# MCU2.net
KiCad netlist of a schematic drawn in Altium Designer
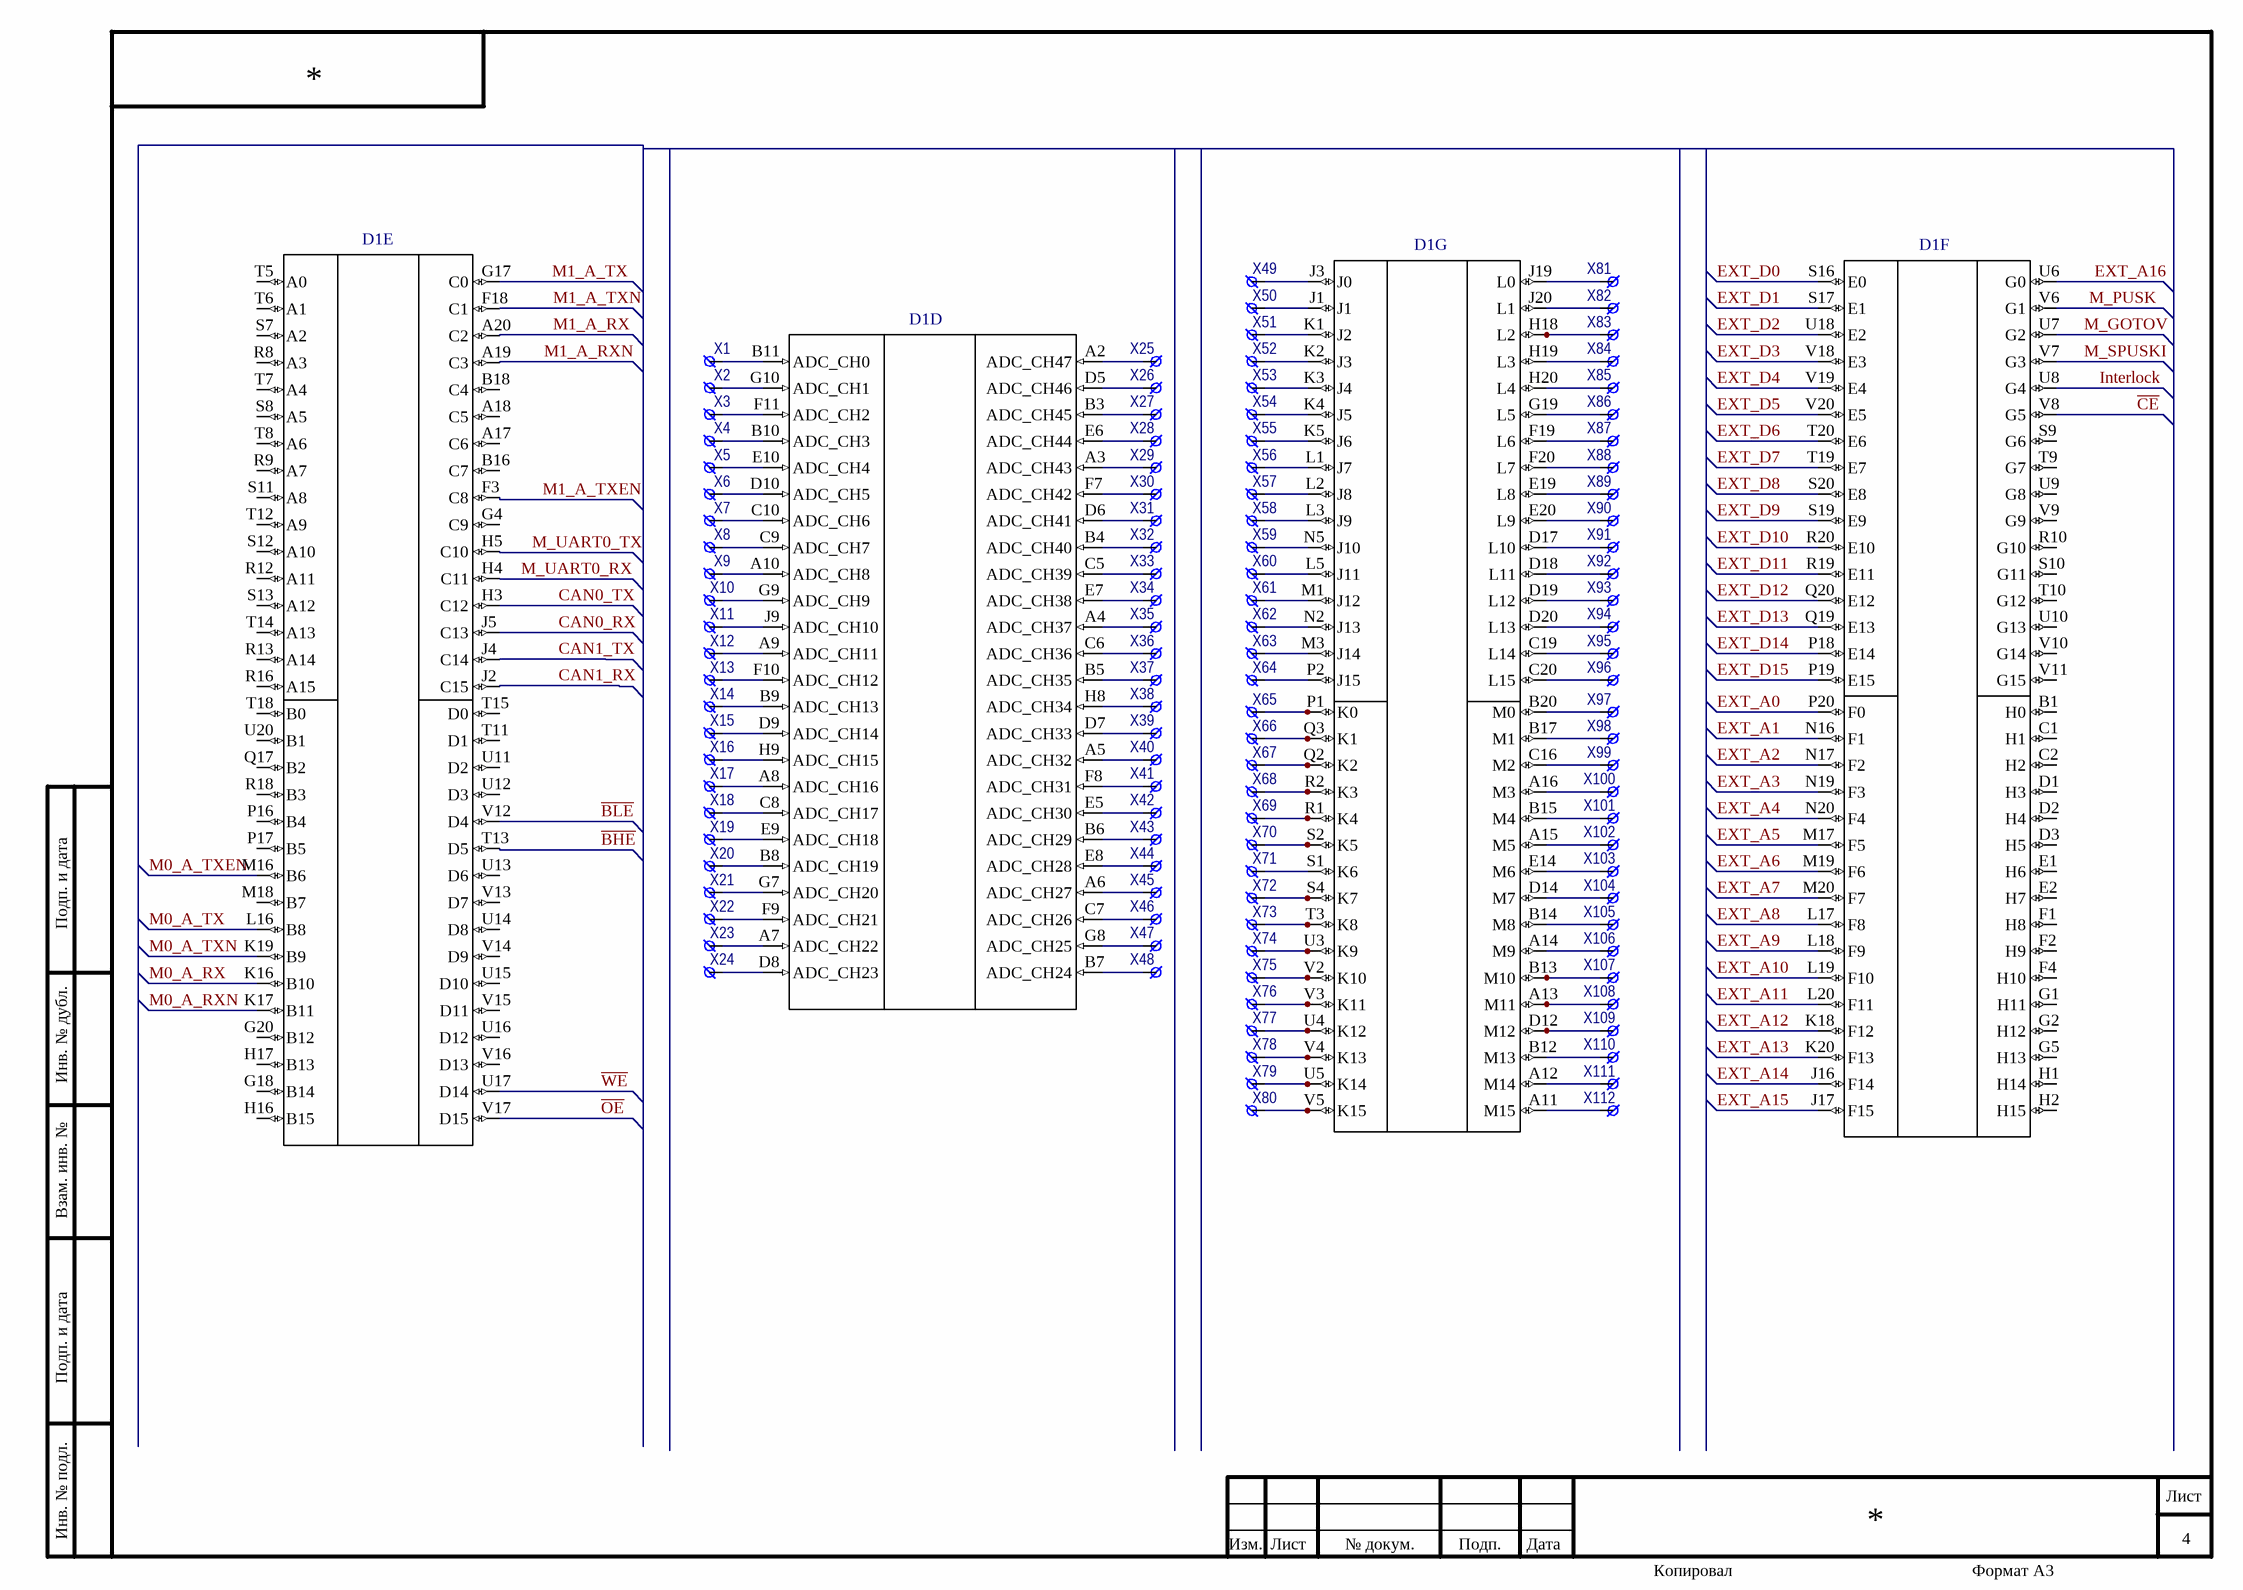
[diagram p0: MCU2.SchDoc]

(export (version "E")
  (design (tool "Eeschema 10.0.6"))
  (components
    (comp (ref "D1")
      (value "1921ВК028")
      (footprint "BGA-400_21.0X21.0MM_LAYOUT20X20_P1.0MM")
      (description "МК 1921ВК028")
      (libsource (lib "Блок вычислительный") (part "1921ВК028"))
    )
    (comp (ref "X1")
      (value "CONT")
      (footprint "ПЛАН_ПЛОЩ")
      (description "CONT1_SMD")
      (fields (field (name "PARTNUMBER") "контактное поле"))
      (libsource (lib "Блок вычислительный") (part "CONT"))
    )
    (comp (ref "X2")
      (value "CONT")
      (footprint "ПЛАН_ПЛОЩ")
      (description "CONT1_SMD")
      (fields (field (name "PARTNUMBER") "контактное поле"))
      (libsource (lib "Блок вычислительный") (part "CONT"))
    )
    (comp (ref "X3")
      (value "CONT")
      (footprint "ПЛАН_ПЛОЩ")
      (description "CONT1_SMD")
      (fields (field (name "PARTNUMBER") "контактное поле"))
      (libsource (lib "Блок вычислительный") (part "CONT"))
    )
    (comp (ref "X4")
      (value "CONT")
      (footprint "ПЛАН_ПЛОЩ")
      (description "CONT1_SMD")
      (fields (field (name "PARTNUMBER") "контактное поле"))
      (libsource (lib "Блок вычислительный") (part "CONT"))
    )
    (comp (ref "X5")
      (value "CONT")
      (footprint "ПЛАН_ПЛОЩ")
      (description "CONT1_SMD")
      (fields (field (name "PARTNUMBER") "контактное поле"))
      (libsource (lib "Блок вычислительный") (part "CONT"))
    )
    (comp (ref "X6")
      (value "CONT")
      (footprint "ПЛАН_ПЛОЩ")
      (description "CONT1_SMD")
      (fields (field (name "PARTNUMBER") "контактное поле"))
      (libsource (lib "Блок вычислительный") (part "CONT"))
    )
    (comp (ref "X7")
      (value "CONT")
      (footprint "ПЛАН_ПЛОЩ")
      (description "CONT1_SMD")
      (fields (field (name "PARTNUMBER") "контактное поле"))
      (libsource (lib "Блок вычислительный") (part "CONT"))
    )
    (comp (ref "X8")
      (value "CONT")
      (footprint "ПЛАН_ПЛОЩ")
      (description "CONT1_SMD")
      (fields (field (name "PARTNUMBER") "контактное поле"))
      (libsource (lib "Блок вычислительный") (part "CONT"))
    )
    (comp (ref "X9")
      (value "CONT")
      (footprint "ПЛАН_ПЛОЩ")
      (description "CONT1_SMD")
      (fields (field (name "PARTNUMBER") "контактное поле"))
      (libsource (lib "Блок вычислительный") (part "CONT"))
    )
    (comp (ref "X10")
      (value "CONT")
      (footprint "ПЛАН_ПЛОЩ")
      (description "CONT1_SMD")
      (fields (field (name "PARTNUMBER") "контактное поле"))
      (libsource (lib "Блок вычислительный") (part "CONT"))
    )
    (comp (ref "X11")
      (value "CONT")
      (footprint "ПЛАН_ПЛОЩ")
      (description "CONT1_SMD")
      (fields (field (name "PARTNUMBER") "контактное поле"))
      (libsource (lib "Блок вычислительный") (part "CONT"))
    )
    (comp (ref "X12")
      (value "CONT")
      (footprint "ПЛАН_ПЛОЩ")
      (description "CONT1_SMD")
      (fields (field (name "PARTNUMBER") "контактное поле"))
      (libsource (lib "Блок вычислительный") (part "CONT"))
    )
    (comp (ref "X13")
      (value "CONT")
      (footprint "ПЛАН_ПЛОЩ")
      (description "CONT1_SMD")
      (fields (field (name "PARTNUMBER") "контактное поле"))
      (libsource (lib "Блок вычислительный") (part "CONT"))
    )
    (comp (ref "X14")
      (value "CONT")
      (footprint "ПЛАН_ПЛОЩ")
      (description "CONT1_SMD")
      (fields (field (name "PARTNUMBER") "контактное поле"))
      (libsource (lib "Блок вычислительный") (part "CONT"))
    )
    (comp (ref "X15")
      (value "CONT")
      (footprint "ПЛАН_ПЛОЩ")
      (description "CONT1_SMD")
      (fields (field (name "PARTNUMBER") "контактное поле"))
      (libsource (lib "Блок вычислительный") (part "CONT"))
    )
    (comp (ref "X16")
      (value "CONT")
      (footprint "ПЛАН_ПЛОЩ")
      (description "CONT1_SMD")
      (fields (field (name "PARTNUMBER") "контактное поле"))
      (libsource (lib "Блок вычислительный") (part "CONT"))
    )
    (comp (ref "X17")
      (value "CONT")
      (footprint "ПЛАН_ПЛОЩ")
      (description "CONT1_SMD")
      (fields (field (name "PARTNUMBER") "контактное поле"))
      (libsource (lib "Блок вычислительный") (part "CONT"))
    )
    (comp (ref "X18")
      (value "CONT")
      (footprint "ПЛАН_ПЛОЩ")
      (description "CONT1_SMD")
      (fields (field (name "PARTNUMBER") "контактное поле"))
      (libsource (lib "Блок вычислительный") (part "CONT"))
    )
    (comp (ref "X19")
      (value "CONT")
      (footprint "ПЛАН_ПЛОЩ")
      (description "CONT1_SMD")
      (fields (field (name "PARTNUMBER") "контактное поле"))
      (libsource (lib "Блок вычислительный") (part "CONT"))
    )
    (comp (ref "X20")
      (value "CONT")
      (footprint "ПЛАН_ПЛОЩ")
      (description "CONT1_SMD")
      (fields (field (name "PARTNUMBER") "контактное поле"))
      (libsource (lib "Блок вычислительный") (part "CONT"))
    )
    (comp (ref "X21")
      (value "CONT")
      (footprint "ПЛАН_ПЛОЩ")
      (description "CONT1_SMD")
      (fields (field (name "PARTNUMBER") "контактное поле"))
      (libsource (lib "Блок вычислительный") (part "CONT"))
    )
    (comp (ref "X22")
      (value "CONT")
      (footprint "ПЛАН_ПЛОЩ")
      (description "CONT1_SMD")
      (fields (field (name "PARTNUMBER") "контактное поле"))
      (libsource (lib "Блок вычислительный") (part "CONT"))
    )
    (comp (ref "X23")
      (value "CONT")
      (footprint "ПЛАН_ПЛОЩ")
      (description "CONT1_SMD")
      (fields (field (name "PARTNUMBER") "контактное поле"))
      (libsource (lib "Блок вычислительный") (part "CONT"))
    )
    (comp (ref "X24")
      (value "CONT")
      (footprint "ПЛАН_ПЛОЩ")
      (description "CONT1_SMD")
      (fields (field (name "PARTNUMBER") "контактное поле"))
      (libsource (lib "Блок вычислительный") (part "CONT"))
    )
    (comp (ref "X25")
      (value "CONT")
      (footprint "ПЛАН_ПЛОЩ")
      (description "CONT1_SMD")
      (fields (field (name "PARTNUMBER") "контактное поле"))
      (libsource (lib "Блок вычислительный") (part "CONT"))
    )
    (comp (ref "X26")
      (value "CONT")
      (footprint "ПЛАН_ПЛОЩ")
      (description "CONT1_SMD")
      (fields (field (name "PARTNUMBER") "контактное поле"))
      (libsource (lib "Блок вычислительный") (part "CONT"))
    )
    (comp (ref "X27")
      (value "CONT")
      (footprint "ПЛАН_ПЛОЩ")
      (description "CONT1_SMD")
      (fields (field (name "PARTNUMBER") "контактное поле"))
      (libsource (lib "Блок вычислительный") (part "CONT"))
    )
    (comp (ref "X28")
      (value "CONT")
      (footprint "ПЛАН_ПЛОЩ")
      (description "CONT1_SMD")
      (fields (field (name "PARTNUMBER") "контактное поле"))
      (libsource (lib "Блок вычислительный") (part "CONT"))
    )
    (comp (ref "X29")
      (value "CONT")
      (footprint "ПЛАН_ПЛОЩ")
      (description "CONT1_SMD")
      (fields (field (name "PARTNUMBER") "контактное поле"))
      (libsource (lib "Блок вычислительный") (part "CONT"))
    )
    (comp (ref "X30")
      (value "CONT")
      (footprint "ПЛАН_ПЛОЩ")
      (description "CONT1_SMD")
      (fields (field (name "PARTNUMBER") "контактное поле"))
      (libsource (lib "Блок вычислительный") (part "CONT"))
    )
    (comp (ref "X31")
      (value "CONT")
      (footprint "ПЛАН_ПЛОЩ")
      (description "CONT1_SMD")
      (fields (field (name "PARTNUMBER") "контактное поле"))
      (libsource (lib "Блок вычислительный") (part "CONT"))
    )
    (comp (ref "X32")
      (value "CONT")
      (footprint "ПЛАН_ПЛОЩ")
      (description "CONT1_SMD")
      (fields (field (name "PARTNUMBER") "контактное поле"))
      (libsource (lib "Блок вычислительный") (part "CONT"))
    )
    (comp (ref "X33")
      (value "CONT")
      (footprint "ПЛАН_ПЛОЩ")
      (description "CONT1_SMD")
      (fields (field (name "PARTNUMBER") "контактное поле"))
      (libsource (lib "Блок вычислительный") (part "CONT"))
    )
    (comp (ref "X34")
      (value "CONT")
      (footprint "ПЛАН_ПЛОЩ")
      (description "CONT1_SMD")
      (fields (field (name "PARTNUMBER") "контактное поле"))
      (libsource (lib "Блок вычислительный") (part "CONT"))
    )
    (comp (ref "X35")
      (value "CONT")
      (footprint "ПЛАН_ПЛОЩ")
      (description "CONT1_SMD")
      (fields (field (name "PARTNUMBER") "контактное поле"))
      (libsource (lib "Блок вычислительный") (part "CONT"))
    )
    (comp (ref "X36")
      (value "CONT")
      (footprint "ПЛАН_ПЛОЩ")
      (description "CONT1_SMD")
      (fields (field (name "PARTNUMBER") "контактное поле"))
      (libsource (lib "Блок вычислительный") (part "CONT"))
    )
    (comp (ref "X37")
      (value "CONT")
      (footprint "ПЛАН_ПЛОЩ")
      (description "CONT1_SMD")
      (fields (field (name "PARTNUMBER") "контактное поле"))
      (libsource (lib "Блок вычислительный") (part "CONT"))
    )
    (comp (ref "X38")
      (value "CONT")
      (footprint "ПЛАН_ПЛОЩ")
      (description "CONT1_SMD")
      (fields (field (name "PARTNUMBER") "контактное поле"))
      (libsource (lib "Блок вычислительный") (part "CONT"))
    )
    (comp (ref "X39")
      (value "CONT")
      (footprint "ПЛАН_ПЛОЩ")
      (description "CONT1_SMD")
      (fields (field (name "PARTNUMBER") "контактное поле"))
      (libsource (lib "Блок вычислительный") (part "CONT"))
    )
    (comp (ref "X40")
      (value "CONT")
      (footprint "ПЛАН_ПЛОЩ")
      (description "CONT1_SMD")
      (fields (field (name "PARTNUMBER") "контактное поле"))
      (libsource (lib "Блок вычислительный") (part "CONT"))
    )
    (comp (ref "X41")
      (value "CONT")
      (footprint "ПЛАН_ПЛОЩ")
      (description "CONT1_SMD")
      (fields (field (name "PARTNUMBER") "контактное поле"))
      (libsource (lib "Блок вычислительный") (part "CONT"))
    )
    (comp (ref "X42")
      (value "CONT")
      (footprint "ПЛАН_ПЛОЩ")
      (description "CONT1_SMD")
      (fields (field (name "PARTNUMBER") "контактное поле"))
      (libsource (lib "Блок вычислительный") (part "CONT"))
    )
    (comp (ref "X43")
      (value "CONT")
      (footprint "ПЛАН_ПЛОЩ")
      (description "CONT1_SMD")
      (fields (field (name "PARTNUMBER") "контактное поле"))
      (libsource (lib "Блок вычислительный") (part "CONT"))
    )
    (comp (ref "X44")
      (value "CONT")
      (footprint "ПЛАН_ПЛОЩ")
      (description "CONT1_SMD")
      (fields (field (name "PARTNUMBER") "контактное поле"))
      (libsource (lib "Блок вычислительный") (part "CONT"))
    )
    (comp (ref "X45")
      (value "CONT")
      (footprint "ПЛАН_ПЛОЩ")
      (description "CONT1_SMD")
      (fields (field (name "PARTNUMBER") "контактное поле"))
      (libsource (lib "Блок вычислительный") (part "CONT"))
    )
    (comp (ref "X46")
      (value "CONT")
      (footprint "ПЛАН_ПЛОЩ")
      (description "CONT1_SMD")
      (fields (field (name "PARTNUMBER") "контактное поле"))
      (libsource (lib "Блок вычислительный") (part "CONT"))
    )
    (comp (ref "X47")
      (value "CONT")
      (footprint "ПЛАН_ПЛОЩ")
      (description "CONT1_SMD")
      (fields (field (name "PARTNUMBER") "контактное поле"))
      (libsource (lib "Блок вычислительный") (part "CONT"))
    )
    (comp (ref "X48")
      (value "CONT")
      (footprint "ПЛАН_ПЛОЩ")
      (description "CONT1_SMD")
      (fields (field (name "PARTNUMBER") "контактное поле"))
      (libsource (lib "Блок вычислительный") (part "CONT"))
    )
    (comp (ref "X49")
      (value "CONT")
      (footprint "ПЛАН_ПЛОЩ")
      (description "CONT1_SMD")
      (fields (field (name "PARTNUMBER") "контактное поле"))
      (libsource (lib "Блок вычислительный") (part "CONT"))
    )
    (comp (ref "X50")
      (value "CONT")
      (footprint "ПЛАН_ПЛОЩ")
      (description "CONT1_SMD")
      (fields (field (name "PARTNUMBER") "контактное поле"))
      (libsource (lib "Блок вычислительный") (part "CONT"))
    )
    (comp (ref "X51")
      (value "CONT")
      (footprint "ПЛАН_ПЛОЩ")
      (description "CONT1_SMD")
      (fields (field (name "PARTNUMBER") "контактное поле"))
      (libsource (lib "Блок вычислительный") (part "CONT"))
    )
    (comp (ref "X52")
      (value "CONT")
      (footprint "ПЛАН_ПЛОЩ")
      (description "CONT1_SMD")
      (fields (field (name "PARTNUMBER") "контактное поле"))
      (libsource (lib "Блок вычислительный") (part "CONT"))
    )
    (comp (ref "X53")
      (value "CONT")
      (footprint "ПЛАН_ПЛОЩ")
      (description "CONT1_SMD")
      (fields (field (name "PARTNUMBER") "контактное поле"))
      (libsource (lib "Блок вычислительный") (part "CONT"))
    )
    (comp (ref "X54")
      (value "CONT")
      (footprint "ПЛАН_ПЛОЩ")
      (description "CONT1_SMD")
      (fields (field (name "PARTNUMBER") "контактное поле"))
      (libsource (lib "Блок вычислительный") (part "CONT"))
    )
    (comp (ref "X55")
      (value "CONT")
      (footprint "ПЛАН_ПЛОЩ")
      (description "CONT1_SMD")
      (fields (field (name "PARTNUMBER") "контактное поле"))
      (libsource (lib "Блок вычислительный") (part "CONT"))
    )
    (comp (ref "X56")
      (value "CONT")
      (footprint "ПЛАН_ПЛОЩ")
      (description "CONT1_SMD")
      (fields (field (name "PARTNUMBER") "контактное поле"))
      (libsource (lib "Блок вычислительный") (part "CONT"))
    )
    (comp (ref "X57")
      (value "CONT")
      (footprint "ПЛАН_ПЛОЩ")
      (description "CONT1_SMD")
      (fields (field (name "PARTNUMBER") "контактное поле"))
      (libsource (lib "Блок вычислительный") (part "CONT"))
    )
    (comp (ref "X58")
      (value "CONT")
      (footprint "ПЛАН_ПЛОЩ")
      (description "CONT1_SMD")
      (fields (field (name "PARTNUMBER") "контактное поле"))
      (libsource (lib "Блок вычислительный") (part "CONT"))
    )
    (comp (ref "X59")
      (value "CONT")
      (footprint "ПЛАН_ПЛОЩ")
      (description "CONT1_SMD")
      (fields (field (name "PARTNUMBER") "контактное поле"))
      (libsource (lib "Блок вычислительный") (part "CONT"))
    )
    (comp (ref "X60")
      (value "CONT")
      (footprint "ПЛАН_ПЛОЩ")
      (description "CONT1_SMD")
      (fields (field (name "PARTNUMBER") "контактное поле"))
      (libsource (lib "Блок вычислительный") (part "CONT"))
    )
    (comp (ref "X61")
      (value "CONT")
      (footprint "ПЛАН_ПЛОЩ")
      (description "CONT1_SMD")
      (fields (field (name "PARTNUMBER") "контактное поле"))
      (libsource (lib "Блок вычислительный") (part "CONT"))
    )
    (comp (ref "X62")
      (value "CONT")
      (footprint "ПЛАН_ПЛОЩ")
      (description "CONT1_SMD")
      (fields (field (name "PARTNUMBER") "контактное поле"))
      (libsource (lib "Блок вычислительный") (part "CONT"))
    )
    (comp (ref "X63")
      (value "CONT")
      (footprint "ПЛАН_ПЛОЩ")
      (description "CONT1_SMD")
      (fields (field (name "PARTNUMBER") "контактное поле"))
      (libsource (lib "Блок вычислительный") (part "CONT"))
    )
    (comp (ref "X64")
      (value "CONT")
      (footprint "ПЛАН_ПЛОЩ")
      (description "CONT1_SMD")
      (fields (field (name "PARTNUMBER") "контактное поле"))
      (libsource (lib "Блок вычислительный") (part "CONT"))
    )
    (comp (ref "X65")
      (value "CONT")
      (footprint "ПЛАН_ПЛОЩ")
      (description "CONT1_SMD")
      (fields (field (name "PARTNUMBER") "контактное поле"))
      (libsource (lib "Блок вычислительный") (part "CONT"))
    )
    (comp (ref "X66")
      (value "CONT")
      (footprint "ПЛАН_ПЛОЩ")
      (description "CONT1_SMD")
      (fields (field (name "PARTNUMBER") "контактное поле"))
      (libsource (lib "Блок вычислительный") (part "CONT"))
    )
    (comp (ref "X67")
      (value "CONT")
      (footprint "ПЛАН_ПЛОЩ")
      (description "CONT1_SMD")
      (fields (field (name "PARTNUMBER") "контактное поле"))
      (libsource (lib "Блок вычислительный") (part "CONT"))
    )
    (comp (ref "X68")
      (value "CONT")
      (footprint "ПЛАН_ПЛОЩ")
      (description "CONT1_SMD")
      (fields (field (name "PARTNUMBER") "контактное поле"))
      (libsource (lib "Блок вычислительный") (part "CONT"))
    )
    (comp (ref "X69")
      (value "CONT")
      (footprint "ПЛАН_ПЛОЩ")
      (description "CONT1_SMD")
      (fields (field (name "PARTNUMBER") "контактное поле"))
      (libsource (lib "Блок вычислительный") (part "CONT"))
    )
    (comp (ref "X70")
      (value "CONT")
      (footprint "ПЛАН_ПЛОЩ")
      (description "CONT1_SMD")
      (fields (field (name "PARTNUMBER") "контактное поле"))
      (libsource (lib "Блок вычислительный") (part "CONT"))
    )
    (comp (ref "X71")
      (value "CONT")
      (footprint "ПЛАН_ПЛОЩ")
      (description "CONT1_SMD")
      (fields (field (name "PARTNUMBER") "контактное поле"))
      (libsource (lib "Блок вычислительный") (part "CONT"))
    )
    (comp (ref "X72")
      (value "CONT")
      (footprint "ПЛАН_ПЛОЩ")
      (description "CONT1_SMD")
      (fields (field (name "PARTNUMBER") "контактное поле"))
      (libsource (lib "Блок вычислительный") (part "CONT"))
    )
    (comp (ref "X73")
      (value "CONT")
      (footprint "ПЛАН_ПЛОЩ")
      (description "CONT1_SMD")
      (fields (field (name "PARTNUMBER") "контактное поле"))
      (libsource (lib "Блок вычислительный") (part "CONT"))
    )
    (comp (ref "X74")
      (value "CONT")
      (footprint "ПЛАН_ПЛОЩ")
      (description "CONT1_SMD")
      (fields (field (name "PARTNUMBER") "контактное поле"))
      (libsource (lib "Блок вычислительный") (part "CONT"))
    )
    (comp (ref "X75")
      (value "CONT")
      (footprint "ПЛАН_ПЛОЩ")
      (description "CONT1_SMD")
      (fields (field (name "PARTNUMBER") "контактное поле"))
      (libsource (lib "Блок вычислительный") (part "CONT"))
    )
    (comp (ref "X76")
      (value "CONT")
      (footprint "ПЛАН_ПЛОЩ")
      (description "CONT1_SMD")
      (fields (field (name "PARTNUMBER") "контактное поле"))
      (libsource (lib "Блок вычислительный") (part "CONT"))
    )
    (comp (ref "X77")
      (value "CONT")
      (footprint "ПЛАН_ПЛОЩ")
      (description "CONT1_SMD")
      (fields (field (name "PARTNUMBER") "контактное поле"))
      (libsource (lib "Блок вычислительный") (part "CONT"))
    )
    (comp (ref "X78")
      (value "CONT")
      (footprint "ПЛАН_ПЛОЩ")
      (description "CONT1_SMD")
      (fields (field (name "PARTNUMBER") "контактное поле"))
      (libsource (lib "Блок вычислительный") (part "CONT"))
    )
    (comp (ref "X79")
      (value "CONT")
      (footprint "ПЛАН_ПЛОЩ")
      (description "CONT1_SMD")
      (fields (field (name "PARTNUMBER") "контактное поле"))
      (libsource (lib "Блок вычислительный") (part "CONT"))
    )
    (comp (ref "X80")
      (value "CONT")
      (footprint "ПЛАН_ПЛОЩ")
      (description "CONT1_SMD")
      (fields (field (name "PARTNUMBER") "контактное поле"))
      (libsource (lib "Блок вычислительный") (part "CONT"))
    )
    (comp (ref "X81")
      (value "CONT")
      (footprint "ПЛАН_ПЛОЩ")
      (description "CONT1_SMD")
      (fields (field (name "PARTNUMBER") "контактное поле"))
      (libsource (lib "Блок вычислительный") (part "CONT"))
    )
    (comp (ref "X82")
      (value "CONT")
      (footprint "ПЛАН_ПЛОЩ")
      (description "CONT1_SMD")
      (fields (field (name "PARTNUMBER") "контактное поле"))
      (libsource (lib "Блок вычислительный") (part "CONT"))
    )
    (comp (ref "X83")
      (value "CONT")
      (footprint "ПЛАН_ПЛОЩ")
      (description "CONT1_SMD")
      (fields (field (name "PARTNUMBER") "контактное поле"))
      (libsource (lib "Блок вычислительный") (part "CONT"))
    )
    (comp (ref "X84")
      (value "CONT")
      (footprint "ПЛАН_ПЛОЩ")
      (description "CONT1_SMD")
      (fields (field (name "PARTNUMBER") "контактное поле"))
      (libsource (lib "Блок вычислительный") (part "CONT"))
    )
    (comp (ref "X85")
      (value "CONT")
      (footprint "ПЛАН_ПЛОЩ")
      (description "CONT1_SMD")
      (fields (field (name "PARTNUMBER") "контактное поле"))
      (libsource (lib "Блок вычислительный") (part "CONT"))
    )
    (comp (ref "X86")
      (value "CONT")
      (footprint "ПЛАН_ПЛОЩ")
      (description "CONT1_SMD")
      (fields (field (name "PARTNUMBER") "контактное поле"))
      (libsource (lib "Блок вычислительный") (part "CONT"))
    )
    (comp (ref "X87")
      (value "CONT")
      (footprint "ПЛАН_ПЛОЩ")
      (description "CONT1_SMD")
      (fields (field (name "PARTNUMBER") "контактное поле"))
      (libsource (lib "Блок вычислительный") (part "CONT"))
    )
    (comp (ref "X88")
      (value "CONT")
      (footprint "ПЛАН_ПЛОЩ")
      (description "CONT1_SMD")
      (fields (field (name "PARTNUMBER") "контактное поле"))
      (libsource (lib "Блок вычислительный") (part "CONT"))
    )
    (comp (ref "X89")
      (value "CONT")
      (footprint "ПЛАН_ПЛОЩ")
      (description "CONT1_SMD")
      (fields (field (name "PARTNUMBER") "контактное поле"))
      (libsource (lib "Блок вычислительный") (part "CONT"))
    )
    (comp (ref "X90")
      (value "CONT")
      (footprint "ПЛАН_ПЛОЩ")
      (description "CONT1_SMD")
      (fields (field (name "PARTNUMBER") "контактное поле"))
      (libsource (lib "Блок вычислительный") (part "CONT"))
    )
    (comp (ref "X91")
      (value "CONT")
      (footprint "ПЛАН_ПЛОЩ")
      (description "CONT1_SMD")
      (fields (field (name "PARTNUMBER") "контактное поле"))
      (libsource (lib "Блок вычислительный") (part "CONT"))
    )
    (comp (ref "X92")
      (value "CONT")
      (footprint "ПЛАН_ПЛОЩ")
      (description "CONT1_SMD")
      (fields (field (name "PARTNUMBER") "контактное поле"))
      (libsource (lib "Блок вычислительный") (part "CONT"))
    )
    (comp (ref "X93")
      (value "CONT")
      (footprint "ПЛАН_ПЛОЩ")
      (description "CONT1_SMD")
      (fields (field (name "PARTNUMBER") "контактное поле"))
      (libsource (lib "Блок вычислительный") (part "CONT"))
    )
    (comp (ref "X94")
      (value "CONT")
      (footprint "ПЛАН_ПЛОЩ")
      (description "CONT1_SMD")
      (fields (field (name "PARTNUMBER") "контактное поле"))
      (libsource (lib "Блок вычислительный") (part "CONT"))
    )
    (comp (ref "X95")
      (value "CONT")
      (footprint "ПЛАН_ПЛОЩ")
      (description "CONT1_SMD")
      (fields (field (name "PARTNUMBER") "контактное поле"))
      (libsource (lib "Блок вычислительный") (part "CONT"))
    )
    (comp (ref "X96")
      (value "CONT")
      (footprint "ПЛАН_ПЛОЩ")
      (description "CONT1_SMD")
      (fields (field (name "PARTNUMBER") "контактное поле"))
      (libsource (lib "Блок вычислительный") (part "CONT"))
    )
    (comp (ref "X97")
      (value "CONT")
      (footprint "ПЛАН_ПЛОЩ")
      (description "CONT1_SMD")
      (fields (field (name "PARTNUMBER") "контактное поле"))
      (libsource (lib "Блок вычислительный") (part "CONT"))
    )
    (comp (ref "X98")
      (value "CONT")
      (footprint "ПЛАН_ПЛОЩ")
      (description "CONT1_SMD")
      (fields (field (name "PARTNUMBER") "контактное поле"))
      (libsource (lib "Блок вычислительный") (part "CONT"))
    )
    (comp (ref "X99")
      (value "CONT")
      (footprint "ПЛАН_ПЛОЩ")
      (description "CONT1_SMD")
      (fields (field (name "PARTNUMBER") "контактное поле"))
      (libsource (lib "Блок вычислительный") (part "CONT"))
    )
    (comp (ref "X100")
      (value "CONT")
      (footprint "ПЛАН_ПЛОЩ")
      (description "CONT1_SMD")
      (fields (field (name "PARTNUMBER") "контактное поле"))
      (libsource (lib "Блок вычислительный") (part "CONT"))
    )
    (comp (ref "X101")
      (value "CONT")
      (footprint "ПЛАН_ПЛОЩ")
      (description "CONT1_SMD")
      (fields (field (name "PARTNUMBER") "контактное поле"))
      (libsource (lib "Блок вычислительный") (part "CONT"))
    )
    (comp (ref "X102")
      (value "CONT")
      (footprint "ПЛАН_ПЛОЩ")
      (description "CONT1_SMD")
      (fields (field (name "PARTNUMBER") "контактное поле"))
      (libsource (lib "Блок вычислительный") (part "CONT"))
    )
    (comp (ref "X103")
      (value "CONT")
      (footprint "ПЛАН_ПЛОЩ")
      (description "CONT1_SMD")
      (fields (field (name "PARTNUMBER") "контактное поле"))
      (libsource (lib "Блок вычислительный") (part "CONT"))
    )
    (comp (ref "X104")
      (value "CONT")
      (footprint "ПЛАН_ПЛОЩ")
      (description "CONT1_SMD")
      (fields (field (name "PARTNUMBER") "контактное поле"))
      (libsource (lib "Блок вычислительный") (part "CONT"))
    )
    (comp (ref "X105")
      (value "CONT")
      (footprint "ПЛАН_ПЛОЩ")
      (description "CONT1_SMD")
      (fields (field (name "PARTNUMBER") "контактное поле"))
      (libsource (lib "Блок вычислительный") (part "CONT"))
    )
    (comp (ref "X106")
      (value "CONT")
      (footprint "ПЛАН_ПЛОЩ")
      (description "CONT1_SMD")
      (fields (field (name "PARTNUMBER") "контактное поле"))
      (libsource (lib "Блок вычислительный") (part "CONT"))
    )
    (comp (ref "X107")
      (value "CONT")
      (footprint "ПЛАН_ПЛОЩ")
      (description "CONT1_SMD")
      (fields (field (name "PARTNUMBER") "контактное поле"))
      (libsource (lib "Блок вычислительный") (part "CONT"))
    )
    (comp (ref "X108")
      (value "CONT")
      (footprint "ПЛАН_ПЛОЩ")
      (description "CONT1_SMD")
      (fields (field (name "PARTNUMBER") "контактное поле"))
      (libsource (lib "Блок вычислительный") (part "CONT"))
    )
    (comp (ref "X109")
      (value "CONT")
      (footprint "ПЛАН_ПЛОЩ")
      (description "CONT1_SMD")
      (fields (field (name "PARTNUMBER") "контактное поле"))
      (libsource (lib "Блок вычислительный") (part "CONT"))
    )
    (comp (ref "X110")
      (value "CONT")
      (footprint "ПЛАН_ПЛОЩ")
      (description "CONT1_SMD")
      (fields (field (name "PARTNUMBER") "контактное поле"))
      (libsource (lib "Блок вычислительный") (part "CONT"))
    )
    (comp (ref "X111")
      (value "CONT")
      (footprint "ПЛАН_ПЛОЩ")
      (description "CONT1_SMD")
      (fields (field (name "PARTNUMBER") "контактное поле"))
      (libsource (lib "Блок вычислительный") (part "CONT"))
    )
    (comp (ref "X112")
      (value "CONT")
      (footprint "ПЛАН_ПЛОЩ")
      (description "CONT1_SMD")
      (fields (field (name "PARTNUMBER") "контактное поле"))
      (libsource (lib "Блок вычислительный") (part "CONT"))
    )
  )
  (nets
    (net (code "1") (name "/BHE") (class "Default")
      (node (ref "D1") (pin "T13") (pinfunction "D5_T13") (pintype "bidirectional"))
    )
    (net (code "2") (name "/BLE") (class "Default")
      (node (ref "D1") (pin "V12") (pinfunction "D4_V12") (pintype "bidirectional"))
    )
    (net (code "3") (name "/CAN0_RX") (class "Default")
      (node (ref "D1") (pin "J5") (pinfunction "C13_J5") (pintype "bidirectional"))
    )
    (net (code "4") (name "/CAN0_TX") (class "Default")
      (node (ref "D1") (pin "H3") (pinfunction "C12_H3") (pintype "bidirectional"))
    )
    (net (code "5") (name "/CAN1_RX") (class "Default")
      (node (ref "D1") (pin "J2") (pinfunction "C15_J2") (pintype "bidirectional"))
    )
    (net (code "6") (name "/CAN1_TX") (class "Default")
      (node (ref "D1") (pin "J4") (pinfunction "C14_J4") (pintype "bidirectional"))
    )
    (net (code "7") (name "/CE") (class "Default")
      (node (ref "D1") (pin "V8") (pinfunction "G5_V8") (pintype "bidirectional"))
    )
    (net (code "8") (name "/EXT_A0") (class "Default")
      (node (ref "D1") (pin "P20") (pinfunction "F0_P20") (pintype "bidirectional"))
    )
    (net (code "9") (name "/EXT_A1") (class "Default")
      (node (ref "D1") (pin "N16") (pinfunction "F1_N16") (pintype "bidirectional"))
    )
    (net (code "10") (name "/EXT_A2") (class "Default")
      (node (ref "D1") (pin "N17") (pinfunction "F2_N17") (pintype "bidirectional"))
    )
    (net (code "11") (name "/EXT_A3") (class "Default")
      (node (ref "D1") (pin "N19") (pinfunction "F3_N19") (pintype "bidirectional"))
    )
    (net (code "12") (name "/EXT_A4") (class "Default")
      (node (ref "D1") (pin "N20") (pinfunction "F4_N20") (pintype "bidirectional"))
    )
    (net (code "13") (name "/EXT_A5") (class "Default")
      (node (ref "D1") (pin "M17") (pinfunction "F5_M17") (pintype "bidirectional"))
    )
    (net (code "14") (name "/EXT_A6") (class "Default")
      (node (ref "D1") (pin "M19") (pinfunction "F6_M19") (pintype "bidirectional"))
    )
    (net (code "15") (name "/EXT_A7") (class "Default")
      (node (ref "D1") (pin "M20") (pinfunction "F7_M20") (pintype "bidirectional"))
    )
    (net (code "16") (name "/EXT_A8") (class "Default")
      (node (ref "D1") (pin "L17") (pinfunction "F8_L17") (pintype "bidirectional"))
    )
    (net (code "17") (name "/EXT_A9") (class "Default")
      (node (ref "D1") (pin "L18") (pinfunction "F9_L18") (pintype "bidirectional"))
    )
    (net (code "18") (name "/EXT_A10") (class "Default")
      (node (ref "D1") (pin "L19") (pinfunction "F10_L19") (pintype "bidirectional"))
    )
    (net (code "19") (name "/EXT_A11") (class "Default")
      (node (ref "D1") (pin "L20") (pinfunction "F11_L20") (pintype "bidirectional"))
    )
    (net (code "20") (name "/EXT_A12") (class "Default")
      (node (ref "D1") (pin "K18") (pinfunction "F12_K18") (pintype "bidirectional"))
    )
    (net (code "21") (name "/EXT_A13") (class "Default")
      (node (ref "D1") (pin "K20") (pinfunction "F13_K20") (pintype "bidirectional"))
    )
    (net (code "22") (name "/EXT_A14") (class "Default")
      (node (ref "D1") (pin "J16") (pinfunction "F14_J16") (pintype "bidirectional"))
    )
    (net (code "23") (name "/EXT_A15") (class "Default")
      (node (ref "D1") (pin "J17") (pinfunction "F15_J17") (pintype "bidirectional"))
    )
    (net (code "24") (name "/EXT_A16") (class "Default")
      (node (ref "D1") (pin "U6") (pinfunction "G0_U6") (pintype "bidirectional"))
    )
    (net (code "25") (name "/EXT_D0") (class "Default")
      (node (ref "D1") (pin "S16") (pinfunction "E0_S16") (pintype "bidirectional"))
    )
    (net (code "26") (name "/EXT_D1") (class "Default")
      (node (ref "D1") (pin "S17") (pinfunction "E1_S17") (pintype "bidirectional"))
    )
    (net (code "27") (name "/EXT_D2") (class "Default")
      (node (ref "D1") (pin "U18") (pinfunction "E2_U18") (pintype "bidirectional"))
    )
    (net (code "28") (name "/EXT_D3") (class "Default")
      (node (ref "D1") (pin "V18") (pinfunction "E3_V18") (pintype "bidirectional"))
    )
    (net (code "29") (name "/EXT_D4") (class "Default")
      (node (ref "D1") (pin "V19") (pinfunction "E4_V19") (pintype "bidirectional"))
    )
    (net (code "30") (name "/EXT_D5") (class "Default")
      (node (ref "D1") (pin "V20") (pinfunction "E5_V20") (pintype "bidirectional"))
    )
    (net (code "31") (name "/EXT_D6") (class "Default")
      (node (ref "D1") (pin "T20") (pinfunction "E6_T20") (pintype "bidirectional"))
    )
    (net (code "32") (name "/EXT_D7") (class "Default")
      (node (ref "D1") (pin "T19") (pinfunction "E7_T19") (pintype "bidirectional"))
    )
    (net (code "33") (name "/EXT_D8") (class "Default")
      (node (ref "D1") (pin "S20") (pinfunction "E8_S20") (pintype "bidirectional"))
    )
    (net (code "34") (name "/EXT_D9") (class "Default")
      (node (ref "D1") (pin "S19") (pinfunction "E9_S19") (pintype "bidirectional"))
    )
    (net (code "35") (name "/EXT_D10") (class "Default")
      (node (ref "D1") (pin "R20") (pinfunction "E10_R20") (pintype "bidirectional"))
    )
    (net (code "36") (name "/EXT_D11") (class "Default")
      (node (ref "D1") (pin "R19") (pinfunction "E11_R19") (pintype "bidirectional"))
    )
    (net (code "37") (name "/EXT_D12") (class "Default")
      (node (ref "D1") (pin "Q20") (pinfunction "E12_Q20") (pintype "bidirectional"))
    )
    (net (code "38") (name "/EXT_D13") (class "Default")
      (node (ref "D1") (pin "Q19") (pinfunction "E13_Q19") (pintype "bidirectional"))
    )
    (net (code "39") (name "/EXT_D14") (class "Default")
      (node (ref "D1") (pin "P18") (pinfunction "E14_P18") (pintype "bidirectional"))
    )
    (net (code "40") (name "/EXT_D15") (class "Default")
      (node (ref "D1") (pin "P19") (pinfunction "E15_P19") (pintype "bidirectional"))
    )
    (net (code "41") (name "/Interlock") (class "Default")
      (node (ref "D1") (pin "U8") (pinfunction "G4_U8") (pintype "bidirectional"))
    )
    (net (code "42") (name "/M0_A_RX") (class "Default")
      (node (ref "D1") (pin "K16") (pinfunction "B10_K16") (pintype "bidirectional"))
    )
    (net (code "43") (name "/M0_A_RXN") (class "Default")
      (node (ref "D1") (pin "K17") (pinfunction "B11_K17") (pintype "bidirectional"))
    )
    (net (code "44") (name "/M0_A_TX") (class "Default")
      (node (ref "D1") (pin "L16") (pinfunction "B8_L16") (pintype "bidirectional"))
    )
    (net (code "45") (name "/M0_A_TXEN") (class "Default")
      (node (ref "D1") (pin "M16") (pinfunction "B6_M16") (pintype "bidirectional"))
    )
    (net (code "46") (name "/M0_A_TXN") (class "Default")
      (node (ref "D1") (pin "K19") (pinfunction "B9_K19") (pintype "bidirectional"))
    )
    (net (code "47") (name "/M1_A_RX") (class "Default")
      (node (ref "D1") (pin "A20") (pinfunction "C2_A20") (pintype "bidirectional"))
    )
    (net (code "48") (name "/M1_A_RXN") (class "Default")
      (node (ref "D1") (pin "A19") (pinfunction "C3_A19") (pintype "bidirectional"))
    )
    (net (code "49") (name "/M1_A_TX") (class "Default")
      (node (ref "D1") (pin "G17") (pinfunction "C0_G17") (pintype "bidirectional"))
    )
    (net (code "50") (name "/M1_A_TXEN") (class "Default")
      (node (ref "D1") (pin "F3") (pinfunction "C8_F3") (pintype "bidirectional"))
    )
    (net (code "51") (name "/M1_A_TXN") (class "Default")
      (node (ref "D1") (pin "F18") (pinfunction "C1_F18") (pintype "bidirectional"))
    )
    (net (code "52") (name "/M_GOTOV") (class "Default")
      (node (ref "D1") (pin "U7") (pinfunction "G2_U7") (pintype "bidirectional"))
    )
    (net (code "53") (name "/M_PUSK") (class "Default")
      (node (ref "D1") (pin "V6") (pinfunction "G1_V6") (pintype "bidirectional"))
    )
    (net (code "54") (name "/M_SPUSKI") (class "Default")
      (node (ref "D1") (pin "V7") (pinfunction "G3_V7") (pintype "bidirectional"))
    )
    (net (code "55") (name "/M_UART0_RX") (class "Default")
      (node (ref "D1") (pin "H4") (pinfunction "C11_H4") (pintype "bidirectional"))
    )
    (net (code "56") (name "/M_UART0_TX") (class "Default")
      (node (ref "D1") (pin "H5") (pinfunction "C10_H5") (pintype "bidirectional"))
    )
    (net (code "57") (name "/OE") (class "Default")
      (node (ref "D1") (pin "V17") (pinfunction "D15_V17") (pintype "bidirectional"))
    )
    (net (code "58") (name "/WE") (class "Default")
      (node (ref "D1") (pin "U17") (pinfunction "D14_U17") (pintype "bidirectional"))
    )
    (net (code "59") (name "Net-(D1-PadJ1)") (class "Default")
      (node (ref "D1") (pin "J1") (pinfunction "J1_J1") (pintype "bidirectional"))
      (node (ref "X50") (pin "1") (pinfunction "1_1") (pintype "passive"))
    )
    (net (code "60") (name "Net-(D1D-ADC_CH0)") (class "Default")
      (node (ref "D1") (pin "B11") (pinfunction "ADC_CH0_B11") (pintype "input"))
      (node (ref "X1") (pin "1") (pinfunction "1_1") (pintype "passive"))
    )
    (net (code "61") (name "Net-(D1D-ADC_CH1)") (class "Default")
      (node (ref "D1") (pin "G10") (pinfunction "ADC_CH1_G10") (pintype "input"))
      (node (ref "X2") (pin "1") (pinfunction "1_1") (pintype "passive"))
    )
    (net (code "62") (name "Net-(D1D-ADC_CH2)") (class "Default")
      (node (ref "D1") (pin "F11") (pinfunction "ADC_CH2_F11") (pintype "input"))
      (node (ref "X3") (pin "1") (pinfunction "1_1") (pintype "passive"))
    )
    (net (code "63") (name "Net-(D1D-ADC_CH3)") (class "Default")
      (node (ref "D1") (pin "B10") (pinfunction "ADC_CH3_B10") (pintype "input"))
      (node (ref "X4") (pin "1") (pinfunction "1_1") (pintype "passive"))
    )
    (net (code "64") (name "Net-(D1D-ADC_CH4)") (class "Default")
      (node (ref "D1") (pin "E10") (pinfunction "ADC_CH4_E10") (pintype "input"))
      (node (ref "X5") (pin "1") (pinfunction "1_1") (pintype "passive"))
    )
    (net (code "65") (name "Net-(D1D-ADC_CH5)") (class "Default")
      (node (ref "D1") (pin "D10") (pinfunction "ADC_CH5_D10") (pintype "input"))
      (node (ref "X6") (pin "1") (pinfunction "1_1") (pintype "passive"))
    )
    (net (code "66") (name "Net-(D1D-ADC_CH6)") (class "Default")
      (node (ref "D1") (pin "C10") (pinfunction "ADC_CH6_C10") (pintype "input"))
      (node (ref "X7") (pin "1") (pinfunction "1_1") (pintype "passive"))
    )
    (net (code "67") (name "Net-(D1D-ADC_CH7)") (class "Default")
      (node (ref "D1") (pin "C9") (pinfunction "ADC_CH7_C9") (pintype "input"))
      (node (ref "X8") (pin "1") (pinfunction "1_1") (pintype "passive"))
    )
    (net (code "68") (name "Net-(D1D-ADC_CH8)") (class "Default")
      (node (ref "D1") (pin "A10") (pinfunction "ADC_CH8_A10") (pintype "input"))
      (node (ref "X9") (pin "1") (pinfunction "1_1") (pintype "passive"))
    )
    (net (code "69") (name "Net-(D1D-ADC_CH9)") (class "Default")
      (node (ref "D1") (pin "G9") (pinfunction "ADC_CH9_G9") (pintype "input"))
      (node (ref "X10") (pin "1") (pinfunction "1_1") (pintype "passive"))
    )
    (net (code "70") (name "Net-(D1D-ADC_CH10)") (class "Default")
      (node (ref "D1") (pin "J9") (pinfunction "ADC_CH10_J9") (pintype "input"))
      (node (ref "X11") (pin "1") (pinfunction "1_1") (pintype "passive"))
    )
    (net (code "71") (name "Net-(D1D-ADC_CH11)") (class "Default")
      (node (ref "D1") (pin "A9") (pinfunction "ADC_CH11_A9") (pintype "input"))
      (node (ref "X12") (pin "1") (pinfunction "1_1") (pintype "passive"))
    )
    (net (code "72") (name "Net-(D1D-ADC_CH12)") (class "Default")
      (node (ref "D1") (pin "F10") (pinfunction "ADC_CH12_F10") (pintype "input"))
      (node (ref "X13") (pin "1") (pinfunction "1_1") (pintype "passive"))
    )
    (net (code "73") (name "Net-(D1D-ADC_CH13)") (class "Default")
      (node (ref "D1") (pin "B9") (pinfunction "ADC_CH13_B9") (pintype "input"))
      (node (ref "X14") (pin "1") (pinfunction "1_1") (pintype "passive"))
    )
    (net (code "74") (name "Net-(D1D-ADC_CH14)") (class "Default")
      (node (ref "D1") (pin "D9") (pinfunction "ADC_CH14_D9") (pintype "input"))
      (node (ref "X15") (pin "1") (pinfunction "1_1") (pintype "passive"))
    )
    (net (code "75") (name "Net-(D1D-ADC_CH15)") (class "Default")
      (node (ref "D1") (pin "H9") (pinfunction "ADC_CH15_H9") (pintype "input"))
      (node (ref "X16") (pin "1") (pinfunction "1_1") (pintype "passive"))
    )
    (net (code "76") (name "Net-(D1D-ADC_CH16)") (class "Default")
      (node (ref "D1") (pin "A8") (pinfunction "ADC_CH16_A8") (pintype "input"))
      (node (ref "X17") (pin "1") (pinfunction "1_1") (pintype "passive"))
    )
    (net (code "77") (name "Net-(D1D-ADC_CH17)") (class "Default")
      (node (ref "D1") (pin "C8") (pinfunction "ADC_CH17_C8") (pintype "input"))
      (node (ref "X18") (pin "1") (pinfunction "1_1") (pintype "passive"))
    )
    (net (code "78") (name "Net-(D1D-ADC_CH18)") (class "Default")
      (node (ref "D1") (pin "E9") (pinfunction "ADC_CH18_E9") (pintype "input"))
      (node (ref "X19") (pin "1") (pinfunction "1_1") (pintype "passive"))
    )
    (net (code "79") (name "Net-(D1D-ADC_CH19)") (class "Default")
      (node (ref "D1") (pin "B8") (pinfunction "ADC_CH19_B8") (pintype "input"))
      (node (ref "X20") (pin "1") (pinfunction "1_1") (pintype "passive"))
    )
    (net (code "80") (name "Net-(D1D-ADC_CH20)") (class "Default")
      (node (ref "D1") (pin "G7") (pinfunction "ADC_CH20_G7") (pintype "input"))
      (node (ref "X21") (pin "1") (pinfunction "1_1") (pintype "passive"))
    )
    (net (code "81") (name "Net-(D1D-ADC_CH21)") (class "Default")
      (node (ref "D1") (pin "F9") (pinfunction "ADC_CH21_F9") (pintype "input"))
      (node (ref "X22") (pin "1") (pinfunction "1_1") (pintype "passive"))
    )
    (net (code "82") (name "Net-(D1D-ADC_CH22)") (class "Default")
      (node (ref "D1") (pin "A7") (pinfunction "ADC_CH22_A7") (pintype "input"))
      (node (ref "X23") (pin "1") (pinfunction "1_1") (pintype "passive"))
    )
    (net (code "83") (name "Net-(D1D-ADC_CH23)") (class "Default")
      (node (ref "D1") (pin "D8") (pinfunction "ADC_CH23_D8") (pintype "input"))
      (node (ref "X24") (pin "1") (pinfunction "1_1") (pintype "passive"))
    )
    (net (code "84") (name "Net-(D1D-ADC_CH24)") (class "Default")
      (node (ref "D1") (pin "B7") (pinfunction "ADC_CH24_B7") (pintype "input"))
      (node (ref "X48") (pin "1") (pinfunction "1_1") (pintype "passive"))
    )
    (net (code "85") (name "Net-(D1D-ADC_CH25)") (class "Default")
      (node (ref "D1") (pin "G8") (pinfunction "ADC_CH25_G8") (pintype "input"))
      (node (ref "X47") (pin "1") (pinfunction "1_1") (pintype "passive"))
    )
    (net (code "86") (name "Net-(D1D-ADC_CH26)") (class "Default")
      (node (ref "D1") (pin "C7") (pinfunction "ADC_CH26_C7") (pintype "input"))
      (node (ref "X46") (pin "1") (pinfunction "1_1") (pintype "passive"))
    )
    (net (code "87") (name "Net-(D1D-ADC_CH27)") (class "Default")
      (node (ref "D1") (pin "A6") (pinfunction "ADC_CH27_A6") (pintype "input"))
      (node (ref "X45") (pin "1") (pinfunction "1_1") (pintype "passive"))
    )
    (net (code "88") (name "Net-(D1D-ADC_CH28)") (class "Default")
      (node (ref "D1") (pin "E8") (pinfunction "ADC_CH28_E8") (pintype "input"))
      (node (ref "X44") (pin "1") (pinfunction "1_1") (pintype "passive"))
    )
    (net (code "89") (name "Net-(D1D-ADC_CH29)") (class "Default")
      (node (ref "D1") (pin "B6") (pinfunction "ADC_CH29_B6") (pintype "input"))
      (node (ref "X43") (pin "1") (pinfunction "1_1") (pintype "passive"))
    )
    (net (code "90") (name "Net-(D1D-ADC_CH30)") (class "Default")
      (node (ref "D1") (pin "E5") (pinfunction "ADC_CH30_E5") (pintype "input"))
      (node (ref "X42") (pin "1") (pinfunction "1_1") (pintype "passive"))
    )
    (net (code "91") (name "Net-(D1D-ADC_CH31)") (class "Default")
      (node (ref "D1") (pin "F8") (pinfunction "ADC_CH31_F8") (pintype "input"))
      (node (ref "X41") (pin "1") (pinfunction "1_1") (pintype "passive"))
    )
    (net (code "92") (name "Net-(D1D-ADC_CH32)") (class "Default")
      (node (ref "D1") (pin "A5") (pinfunction "ADC_CH32_A5") (pintype "input"))
      (node (ref "X40") (pin "1") (pinfunction "1_1") (pintype "passive"))
    )
    (net (code "93") (name "Net-(D1D-ADC_CH33)") (class "Default")
      (node (ref "D1") (pin "D7") (pinfunction "ADC_CH33_D7") (pintype "input"))
      (node (ref "X39") (pin "1") (pinfunction "1_1") (pintype "passive"))
    )
    (net (code "94") (name "Net-(D1D-ADC_CH34)") (class "Default")
      (node (ref "D1") (pin "H8") (pinfunction "ADC_CH34_H8") (pintype "input"))
      (node (ref "X38") (pin "1") (pinfunction "1_1") (pintype "passive"))
    )
    (net (code "95") (name "Net-(D1D-ADC_CH35)") (class "Default")
      (node (ref "D1") (pin "B5") (pinfunction "ADC_CH35_B5") (pintype "input"))
      (node (ref "X37") (pin "1") (pinfunction "1_1") (pintype "passive"))
    )
    (net (code "96") (name "Net-(D1D-ADC_CH36)") (class "Default")
      (node (ref "D1") (pin "C6") (pinfunction "ADC_CH36_C6") (pintype "input"))
      (node (ref "X36") (pin "1") (pinfunction "1_1") (pintype "passive"))
    )
    (net (code "97") (name "Net-(D1D-ADC_CH37)") (class "Default")
      (node (ref "D1") (pin "A4") (pinfunction "ADC_CH37_A4") (pintype "input"))
      (node (ref "X35") (pin "1") (pinfunction "1_1") (pintype "passive"))
    )
    (net (code "98") (name "Net-(D1D-ADC_CH38)") (class "Default")
      (node (ref "D1") (pin "E7") (pinfunction "ADC_CH38_E7") (pintype "input"))
      (node (ref "X34") (pin "1") (pinfunction "1_1") (pintype "passive"))
    )
    (net (code "99") (name "Net-(D1D-ADC_CH39)") (class "Default")
      (node (ref "D1") (pin "C5") (pinfunction "ADC_CH39_C5") (pintype "input"))
      (node (ref "X33") (pin "1") (pinfunction "1_1") (pintype "passive"))
    )
    (net (code "100") (name "Net-(D1D-ADC_CH40)") (class "Default")
      (node (ref "D1") (pin "B4") (pinfunction "ADC_CH40_B4") (pintype "input"))
      (node (ref "X32") (pin "1") (pinfunction "1_1") (pintype "passive"))
    )
    (net (code "101") (name "Net-(D1D-ADC_CH41)") (class "Default")
      (node (ref "D1") (pin "D6") (pinfunction "ADC_CH41_D6") (pintype "input"))
      (node (ref "X31") (pin "1") (pinfunction "1_1") (pintype "passive"))
    )
    (net (code "102") (name "Net-(D1D-ADC_CH42)") (class "Default")
      (node (ref "D1") (pin "F7") (pinfunction "ADC_CH42_F7") (pintype "input"))
      (node (ref "X30") (pin "1") (pinfunction "1_1") (pintype "passive"))
    )
    (net (code "103") (name "Net-(D1D-ADC_CH43)") (class "Default")
      (node (ref "D1") (pin "A3") (pinfunction "ADC_CH43_A3") (pintype "input"))
      (node (ref "X29") (pin "1") (pinfunction "1_1") (pintype "passive"))
    )
    (net (code "104") (name "Net-(D1D-ADC_CH44)") (class "Default")
      (node (ref "D1") (pin "E6") (pinfunction "ADC_CH44_E6") (pintype "input"))
      (node (ref "X28") (pin "1") (pinfunction "1_1") (pintype "passive"))
    )
    (net (code "105") (name "Net-(D1D-ADC_CH45)") (class "Default")
      (node (ref "D1") (pin "B3") (pinfunction "ADC_CH45_B3") (pintype "input"))
      (node (ref "X27") (pin "1") (pinfunction "1_1") (pintype "passive"))
    )
    (net (code "106") (name "Net-(D1D-ADC_CH46)") (class "Default")
      (node (ref "D1") (pin "D5") (pinfunction "ADC_CH46_D5") (pintype "input"))
      (node (ref "X26") (pin "1") (pinfunction "1_1") (pintype "passive"))
    )
    (net (code "107") (name "Net-(D1D-ADC_CH47)") (class "Default")
      (node (ref "D1") (pin "A2") (pinfunction "ADC_CH47_A2") (pintype "input"))
      (node (ref "X25") (pin "1") (pinfunction "1_1") (pintype "passive"))
    )
    (net (code "108") (name "Net-(D1G-J0)") (class "Default")
      (node (ref "D1") (pin "J3") (pinfunction "J0_J3") (pintype "bidirectional"))
      (node (ref "X49") (pin "1") (pinfunction "1_1") (pintype "passive"))
    )
    (net (code "109") (name "Net-(D1G-J2)") (class "Default")
      (node (ref "D1") (pin "K1") (pinfunction "J2_K1") (pintype "bidirectional"))
      (node (ref "X51") (pin "1") (pinfunction "1_1") (pintype "passive"))
    )
    (net (code "110") (name "Net-(D1G-J3)") (class "Default")
      (node (ref "D1") (pin "K2") (pinfunction "J3_K2") (pintype "bidirectional"))
      (node (ref "X52") (pin "1") (pinfunction "1_1") (pintype "passive"))
    )
    (net (code "111") (name "Net-(D1G-J4)") (class "Default")
      (node (ref "D1") (pin "K3") (pinfunction "J4_K3") (pintype "bidirectional"))
      (node (ref "X53") (pin "1") (pinfunction "1_1") (pintype "passive"))
    )
    (net (code "112") (name "Net-(D1G-J5)") (class "Default")
      (node (ref "D1") (pin "K4") (pinfunction "J5_K4") (pintype "bidirectional"))
      (node (ref "X54") (pin "1") (pinfunction "1_1") (pintype "passive"))
    )
    (net (code "113") (name "Net-(D1G-J6)") (class "Default")
      (node (ref "D1") (pin "K5") (pinfunction "J6_K5") (pintype "bidirectional"))
      (node (ref "X55") (pin "1") (pinfunction "1_1") (pintype "passive"))
    )
    (net (code "114") (name "Net-(D1G-J7)") (class "Default")
      (node (ref "D1") (pin "L1") (pinfunction "J7_L1") (pintype "bidirectional"))
      (node (ref "X56") (pin "1") (pinfunction "1_1") (pintype "passive"))
    )
    (net (code "115") (name "Net-(D1G-J8)") (class "Default")
      (node (ref "D1") (pin "L2") (pinfunction "J8_L2") (pintype "bidirectional"))
      (node (ref "X57") (pin "1") (pinfunction "1_1") (pintype "passive"))
    )
    (net (code "116") (name "Net-(D1G-J9)") (class "Default")
      (node (ref "D1") (pin "L3") (pinfunction "J9_L3") (pintype "bidirectional"))
      (node (ref "X58") (pin "1") (pinfunction "1_1") (pintype "passive"))
    )
    (net (code "117") (name "Net-(D1G-J10)") (class "Default")
      (node (ref "D1") (pin "N5") (pinfunction "J10_N5") (pintype "bidirectional"))
      (node (ref "X59") (pin "1") (pinfunction "1_1") (pintype "passive"))
    )
    (net (code "118") (name "Net-(D1G-J11)") (class "Default")
      (node (ref "D1") (pin "L5") (pinfunction "J11_L5") (pintype "bidirectional"))
      (node (ref "X60") (pin "1") (pinfunction "1_1") (pintype "passive"))
    )
    (net (code "119") (name "Net-(D1G-J12)") (class "Default")
      (node (ref "D1") (pin "M1") (pinfunction "J12_M1") (pintype "bidirectional"))
      (node (ref "X61") (pin "1") (pinfunction "1_1") (pintype "passive"))
    )
    (net (code "120") (name "Net-(D1G-J13)") (class "Default")
      (node (ref "D1") (pin "N2") (pinfunction "J13_N2") (pintype "bidirectional"))
      (node (ref "X62") (pin "1") (pinfunction "1_1") (pintype "passive"))
    )
    (net (code "121") (name "Net-(D1G-J14)") (class "Default")
      (node (ref "D1") (pin "M3") (pinfunction "J14_M3") (pintype "bidirectional"))
      (node (ref "X63") (pin "1") (pinfunction "1_1") (pintype "passive"))
    )
    (net (code "122") (name "Net-(D1G-J15)") (class "Default")
      (node (ref "D1") (pin "P2") (pinfunction "J15_P2") (pintype "bidirectional"))
      (node (ref "X64") (pin "1") (pinfunction "1_1") (pintype "passive"))
    )
    (net (code "123") (name "Net-(D1G-K0)") (class "Default")
      (node (ref "D1") (pin "P1") (pinfunction "K0_P1") (pintype "bidirectional"))
      (node (ref "X65") (pin "1") (pinfunction "1_1") (pintype "passive"))
    )
    (net (code "124") (name "Net-(D1G-K1)") (class "Default")
      (node (ref "D1") (pin "Q3") (pinfunction "K1_Q3") (pintype "bidirectional"))
      (node (ref "X66") (pin "1") (pinfunction "1_1") (pintype "passive"))
    )
    (net (code "125") (name "Net-(D1G-K2)") (class "Default")
      (node (ref "D1") (pin "Q2") (pinfunction "K2_Q2") (pintype "bidirectional"))
      (node (ref "X67") (pin "1") (pinfunction "1_1") (pintype "passive"))
    )
    (net (code "126") (name "Net-(D1G-K3)") (class "Default")
      (node (ref "D1") (pin "R2") (pinfunction "K3_R2") (pintype "bidirectional"))
      (node (ref "X68") (pin "1") (pinfunction "1_1") (pintype "passive"))
    )
    (net (code "127") (name "Net-(D1G-K4)") (class "Default")
      (node (ref "D1") (pin "R1") (pinfunction "K4_R1") (pintype "bidirectional"))
      (node (ref "X69") (pin "1") (pinfunction "1_1") (pintype "passive"))
    )
    (net (code "128") (name "Net-(D1G-K5)") (class "Default")
      (node (ref "D1") (pin "S2") (pinfunction "K5_S2") (pintype "bidirectional"))
      (node (ref "X70") (pin "1") (pinfunction "1_1") (pintype "passive"))
    )
    (net (code "129") (name "Net-(D1G-K6)") (class "Default")
      (node (ref "D1") (pin "S1") (pinfunction "K6_S1") (pintype "bidirectional"))
      (node (ref "X71") (pin "1") (pinfunction "1_1") (pintype "passive"))
    )
    (net (code "130") (name "Net-(D1G-K7)") (class "Default")
      (node (ref "D1") (pin "S4") (pinfunction "K7_S4") (pintype "bidirectional"))
      (node (ref "X72") (pin "1") (pinfunction "1_1") (pintype "passive"))
    )
    (net (code "131") (name "Net-(D1G-K8)") (class "Default")
      (node (ref "D1") (pin "T3") (pinfunction "K8_T3") (pintype "bidirectional"))
      (node (ref "X73") (pin "1") (pinfunction "1_1") (pintype "passive"))
    )
    (net (code "132") (name "Net-(D1G-K9)") (class "Default")
      (node (ref "D1") (pin "U3") (pinfunction "K9_U3") (pintype "bidirectional"))
      (node (ref "X74") (pin "1") (pinfunction "1_1") (pintype "passive"))
    )
    (net (code "133") (name "Net-(D1G-K10)") (class "Default")
      (node (ref "D1") (pin "V2") (pinfunction "K10_V2") (pintype "bidirectional"))
      (node (ref "X75") (pin "1") (pinfunction "1_1") (pintype "passive"))
    )
    (net (code "134") (name "Net-(D1G-K11)") (class "Default")
      (node (ref "D1") (pin "V3") (pinfunction "K11_V3") (pintype "bidirectional"))
      (node (ref "X76") (pin "1") (pinfunction "1_1") (pintype "passive"))
    )
    (net (code "135") (name "Net-(D1G-K12)") (class "Default")
      (node (ref "D1") (pin "U4") (pinfunction "K12_U4") (pintype "bidirectional"))
      (node (ref "X77") (pin "1") (pinfunction "1_1") (pintype "passive"))
    )
    (net (code "136") (name "Net-(D1G-K13)") (class "Default")
      (node (ref "D1") (pin "V4") (pinfunction "K13_V4") (pintype "bidirectional"))
      (node (ref "X78") (pin "1") (pinfunction "1_1") (pintype "passive"))
    )
    (net (code "137") (name "Net-(D1G-K14)") (class "Default")
      (node (ref "D1") (pin "U5") (pinfunction "K14_U5") (pintype "bidirectional"))
      (node (ref "X79") (pin "1") (pinfunction "1_1") (pintype "passive"))
    )
    (net (code "138") (name "Net-(D1G-K15)") (class "Default")
      (node (ref "D1") (pin "V5") (pinfunction "K15_V5") (pintype "bidirectional"))
      (node (ref "X80") (pin "1") (pinfunction "1_1") (pintype "passive"))
    )
    (net (code "139") (name "Net-(D1G-L0)") (class "Default")
      (node (ref "D1") (pin "J19") (pinfunction "L0_J19") (pintype "bidirectional"))
      (node (ref "X81") (pin "1") (pinfunction "1_1") (pintype "passive"))
    )
    (net (code "140") (name "Net-(D1G-L1)") (class "Default")
      (node (ref "D1") (pin "J20") (pinfunction "L1_J20") (pintype "bidirectional"))
      (node (ref "X82") (pin "1") (pinfunction "1_1") (pintype "passive"))
    )
    (net (code "141") (name "Net-(D1G-L2)") (class "Default")
      (node (ref "D1") (pin "H18") (pinfunction "L2_H18") (pintype "bidirectional"))
      (node (ref "X83") (pin "1") (pinfunction "1_1") (pintype "passive"))
    )
    (net (code "142") (name "Net-(D1G-L3)") (class "Default")
      (node (ref "D1") (pin "H19") (pinfunction "L3_H19") (pintype "bidirectional"))
      (node (ref "X84") (pin "1") (pinfunction "1_1") (pintype "passive"))
    )
    (net (code "143") (name "Net-(D1G-L4)") (class "Default")
      (node (ref "D1") (pin "H20") (pinfunction "L4_H20") (pintype "bidirectional"))
      (node (ref "X85") (pin "1") (pinfunction "1_1") (pintype "passive"))
    )
    (net (code "144") (name "Net-(D1G-L5)") (class "Default")
      (node (ref "D1") (pin "G19") (pinfunction "L5_G19") (pintype "bidirectional"))
      (node (ref "X86") (pin "1") (pinfunction "1_1") (pintype "passive"))
    )
    (net (code "145") (name "Net-(D1G-L6)") (class "Default")
      (node (ref "D1") (pin "F19") (pinfunction "L6_F19") (pintype "bidirectional"))
      (node (ref "X87") (pin "1") (pinfunction "1_1") (pintype "passive"))
    )
    (net (code "146") (name "Net-(D1G-L7)") (class "Default")
      (node (ref "D1") (pin "F20") (pinfunction "L7_F20") (pintype "bidirectional"))
      (node (ref "X88") (pin "1") (pinfunction "1_1") (pintype "passive"))
    )
    (net (code "147") (name "Net-(D1G-L8)") (class "Default")
      (node (ref "D1") (pin "E19") (pinfunction "L8_E19") (pintype "bidirectional"))
      (node (ref "X89") (pin "1") (pinfunction "1_1") (pintype "passive"))
    )
    (net (code "148") (name "Net-(D1G-L9)") (class "Default")
      (node (ref "D1") (pin "E20") (pinfunction "L9_E20") (pintype "bidirectional"))
      (node (ref "X90") (pin "1") (pinfunction "1_1") (pintype "passive"))
    )
    (net (code "149") (name "Net-(D1G-L10)") (class "Default")
      (node (ref "D1") (pin "D17") (pinfunction "L10_D17") (pintype "bidirectional"))
      (node (ref "X91") (pin "1") (pinfunction "1_1") (pintype "passive"))
    )
    (net (code "150") (name "Net-(D1G-L11)") (class "Default")
      (node (ref "D1") (pin "D18") (pinfunction "L11_D18") (pintype "bidirectional"))
      (node (ref "X92") (pin "1") (pinfunction "1_1") (pintype "passive"))
    )
    (net (code "151") (name "Net-(D1G-L12)") (class "Default")
      (node (ref "D1") (pin "D19") (pinfunction "L12_D19") (pintype "bidirectional"))
      (node (ref "X93") (pin "1") (pinfunction "1_1") (pintype "passive"))
    )
    (net (code "152") (name "Net-(D1G-L13)") (class "Default")
      (node (ref "D1") (pin "D20") (pinfunction "L13_D20") (pintype "bidirectional"))
      (node (ref "X94") (pin "1") (pinfunction "1_1") (pintype "passive"))
    )
    (net (code "153") (name "Net-(D1G-L14)") (class "Default")
      (node (ref "D1") (pin "C19") (pinfunction "L14_C19") (pintype "bidirectional"))
      (node (ref "X95") (pin "1") (pinfunction "1_1") (pintype "passive"))
    )
    (net (code "154") (name "Net-(D1G-L15)") (class "Default")
      (node (ref "D1") (pin "C20") (pinfunction "L15_C20") (pintype "bidirectional"))
      (node (ref "X96") (pin "1") (pinfunction "1_1") (pintype "passive"))
    )
    (net (code "155") (name "Net-(D1G-M0)") (class "Default")
      (node (ref "D1") (pin "B20") (pinfunction "M0_B20") (pintype "bidirectional"))
      (node (ref "X97") (pin "1") (pinfunction "1_1") (pintype "passive"))
    )
    (net (code "156") (name "Net-(D1G-M1)") (class "Default")
      (node (ref "D1") (pin "B17") (pinfunction "M1_B17") (pintype "bidirectional"))
      (node (ref "X98") (pin "1") (pinfunction "1_1") (pintype "passive"))
    )
    (net (code "157") (name "Net-(D1G-M2)") (class "Default")
      (node (ref "D1") (pin "C16") (pinfunction "M2_C16") (pintype "bidirectional"))
      (node (ref "X99") (pin "1") (pinfunction "1_1") (pintype "passive"))
    )
    (net (code "158") (name "Net-(D1G-M3)") (class "Default")
      (node (ref "D1") (pin "A16") (pinfunction "M3_A16") (pintype "bidirectional"))
      (node (ref "X100") (pin "1") (pinfunction "1_1") (pintype "passive"))
    )
    (net (code "159") (name "Net-(D1G-M4)") (class "Default")
      (node (ref "D1") (pin "B15") (pinfunction "M4_B15") (pintype "bidirectional"))
      (node (ref "X101") (pin "1") (pinfunction "1_1") (pintype "passive"))
    )
    (net (code "160") (name "Net-(D1G-M5)") (class "Default")
      (node (ref "D1") (pin "A15") (pinfunction "M5_A15") (pintype "bidirectional"))
      (node (ref "X102") (pin "1") (pinfunction "1_1") (pintype "passive"))
    )
    (net (code "161") (name "Net-(D1G-M6)") (class "Default")
      (node (ref "D1") (pin "E14") (pinfunction "M6_E14") (pintype "bidirectional"))
      (node (ref "X103") (pin "1") (pinfunction "1_1") (pintype "passive"))
    )
    (net (code "162") (name "Net-(D1G-M7)") (class "Default")
      (node (ref "D1") (pin "D14") (pinfunction "M7_D14") (pintype "bidirectional"))
      (node (ref "X104") (pin "1") (pinfunction "1_1") (pintype "passive"))
    )
    (net (code "163") (name "Net-(D1G-M8)") (class "Default")
      (node (ref "D1") (pin "B14") (pinfunction "M8_B14") (pintype "bidirectional"))
      (node (ref "X105") (pin "1") (pinfunction "1_1") (pintype "passive"))
    )
    (net (code "164") (name "Net-(D1G-M9)") (class "Default")
      (node (ref "D1") (pin "A14") (pinfunction "M9_A14") (pintype "bidirectional"))
      (node (ref "X106") (pin "1") (pinfunction "1_1") (pintype "passive"))
    )
    (net (code "165") (name "Net-(D1G-M10)") (class "Default")
      (node (ref "D1") (pin "B13") (pinfunction "M10_B13") (pintype "bidirectional"))
      (node (ref "X107") (pin "1") (pinfunction "1_1") (pintype "passive"))
    )
    (net (code "166") (name "Net-(D1G-M11)") (class "Default")
      (node (ref "D1") (pin "A13") (pinfunction "M11_A13") (pintype "bidirectional"))
      (node (ref "X108") (pin "1") (pinfunction "1_1") (pintype "passive"))
    )
    (net (code "167") (name "Net-(D1G-M12)") (class "Default")
      (node (ref "D1") (pin "D12") (pinfunction "M12_D12") (pintype "bidirectional"))
      (node (ref "X109") (pin "1") (pinfunction "1_1") (pintype "passive"))
    )
    (net (code "168") (name "Net-(D1G-M13)") (class "Default")
      (node (ref "D1") (pin "B12") (pinfunction "M13_B12") (pintype "bidirectional"))
      (node (ref "X110") (pin "1") (pinfunction "1_1") (pintype "passive"))
    )
    (net (code "169") (name "Net-(D1G-M14)") (class "Default")
      (node (ref "D1") (pin "A12") (pinfunction "M14_A12") (pintype "bidirectional"))
      (node (ref "X111") (pin "1") (pinfunction "1_1") (pintype "passive"))
    )
    (net (code "170") (name "Net-(D1G-M15)") (class "Default")
      (node (ref "D1") (pin "A11") (pinfunction "M15_A11") (pintype "bidirectional"))
      (node (ref "X112") (pin "1") (pinfunction "1_1") (pintype "passive"))
    )
    (net (code "171") (name "unconnected-(D1E-A0-PadT5)") (class "Default")
      (node (ref "D1") (pin "T5") (pinfunction "A0_T5") (pintype "bidirectional"))
    )
    (net (code "172") (name "unconnected-(D1E-A1-PadT6)") (class "Default")
      (node (ref "D1") (pin "T6") (pinfunction "A1_T6") (pintype "bidirectional"))
    )
    (net (code "173") (name "unconnected-(D1E-A2-PadS7)") (class "Default")
      (node (ref "D1") (pin "S7") (pinfunction "A2_S7") (pintype "bidirectional"))
    )
    (net (code "174") (name "unconnected-(D1E-A3-PadR8)") (class "Default")
      (node (ref "D1") (pin "R8") (pinfunction "A3_R8") (pintype "bidirectional"))
    )
    (net (code "175") (name "unconnected-(D1E-A4-PadT7)") (class "Default")
      (node (ref "D1") (pin "T7") (pinfunction "A4_T7") (pintype "bidirectional"))
    )
    (net (code "176") (name "unconnected-(D1E-A5-PadS8)") (class "Default")
      (node (ref "D1") (pin "S8") (pinfunction "A5_S8") (pintype "bidirectional"))
    )
    (net (code "177") (name "unconnected-(D1E-A6-PadT8)") (class "Default")
      (node (ref "D1") (pin "T8") (pinfunction "A6_T8") (pintype "bidirectional"))
    )
    (net (code "178") (name "unconnected-(D1E-A7-PadR9)") (class "Default")
      (node (ref "D1") (pin "R9") (pinfunction "A7_R9") (pintype "bidirectional"))
    )
    (net (code "179") (name "unconnected-(D1E-A8-PadS11)") (class "Default")
      (node (ref "D1") (pin "S11") (pinfunction "A8_S11") (pintype "bidirectional"))
    )
    (net (code "180") (name "unconnected-(D1E-A9-PadT12)") (class "Default")
      (node (ref "D1") (pin "T12") (pinfunction "A9_T12") (pintype "bidirectional"))
    )
    (net (code "181") (name "unconnected-(D1E-A10-PadS12)") (class "Default")
      (node (ref "D1") (pin "S12") (pinfunction "A10_S12") (pintype "bidirectional"))
    )
    (net (code "182") (name "unconnected-(D1E-A11-PadR12)") (class "Default")
      (node (ref "D1") (pin "R12") (pinfunction "A11_R12") (pintype "bidirectional"))
    )
    (net (code "183") (name "unconnected-(D1E-A12-PadS13)") (class "Default")
      (node (ref "D1") (pin "S13") (pinfunction "A12_S13") (pintype "bidirectional"))
    )
    (net (code "184") (name "unconnected-(D1E-A13-PadT14)") (class "Default")
      (node (ref "D1") (pin "T14") (pinfunction "A13_T14") (pintype "bidirectional"))
    )
    (net (code "185") (name "unconnected-(D1E-A14-PadR13)") (class "Default")
      (node (ref "D1") (pin "R13") (pinfunction "A14_R13") (pintype "bidirectional"))
    )
    (net (code "186") (name "unconnected-(D1E-A15-PadR16)") (class "Default")
      (node (ref "D1") (pin "R16") (pinfunction "A15_R16") (pintype "bidirectional"))
    )
    (net (code "187") (name "unconnected-(D1E-B0-PadT18)") (class "Default")
      (node (ref "D1") (pin "T18") (pinfunction "B0_T18") (pintype "bidirectional"))
    )
    (net (code "188") (name "unconnected-(D1E-B1-PadU20)") (class "Default")
      (node (ref "D1") (pin "U20") (pinfunction "B1_U20") (pintype "bidirectional"))
    )
    (net (code "189") (name "unconnected-(D1E-B2-PadQ17)") (class "Default")
      (node (ref "D1") (pin "Q17") (pinfunction "B2_Q17") (pintype "bidirectional"))
    )
    (net (code "190") (name "unconnected-(D1E-B3-PadR18)") (class "Default")
      (node (ref "D1") (pin "R18") (pinfunction "B3_R18") (pintype "bidirectional"))
    )
    (net (code "191") (name "unconnected-(D1E-B4-PadP16)") (class "Default")
      (node (ref "D1") (pin "P16") (pinfunction "B4_P16") (pintype "bidirectional"))
    )
    (net (code "192") (name "unconnected-(D1E-B5-PadP17)") (class "Default")
      (node (ref "D1") (pin "P17") (pinfunction "B5_P17") (pintype "bidirectional"))
    )
    (net (code "193") (name "unconnected-(D1E-B7-PadM18)") (class "Default")
      (node (ref "D1") (pin "M18") (pinfunction "B7_M18") (pintype "bidirectional"))
    )
    (net (code "194") (name "unconnected-(D1E-B12-PadG20)") (class "Default")
      (node (ref "D1") (pin "G20") (pinfunction "B12_G20") (pintype "bidirectional"))
    )
    (net (code "195") (name "unconnected-(D1E-B13-PadH17)") (class "Default")
      (node (ref "D1") (pin "H17") (pinfunction "B13_H17") (pintype "bidirectional"))
    )
    (net (code "196") (name "unconnected-(D1E-B14-PadG18)") (class "Default")
      (node (ref "D1") (pin "G18") (pinfunction "B14_G18") (pintype "bidirectional"))
    )
    (net (code "197") (name "unconnected-(D1E-B15-PadH16)") (class "Default")
      (node (ref "D1") (pin "H16") (pinfunction "B15_H16") (pintype "bidirectional"))
    )
    (net (code "198") (name "unconnected-(D1E-C4-PadB18)") (class "Default")
      (node (ref "D1") (pin "B18") (pinfunction "C4_B18") (pintype "bidirectional"))
    )
    (net (code "199") (name "unconnected-(D1E-C5-PadA18)") (class "Default")
      (node (ref "D1") (pin "A18") (pinfunction "C5_A18") (pintype "bidirectional"))
    )
    (net (code "200") (name "unconnected-(D1E-C6-PadA17)") (class "Default")
      (node (ref "D1") (pin "A17") (pinfunction "C6_A17") (pintype "bidirectional"))
    )
    (net (code "201") (name "unconnected-(D1E-C7-PadB16)") (class "Default")
      (node (ref "D1") (pin "B16") (pinfunction "C7_B16") (pintype "bidirectional"))
    )
    (net (code "202") (name "unconnected-(D1E-C9-PadG4)") (class "Default")
      (node (ref "D1") (pin "G4") (pinfunction "C9_G4") (pintype "bidirectional"))
    )
    (net (code "203") (name "unconnected-(D1E-D0-PadT15)") (class "Default")
      (node (ref "D1") (pin "T15") (pinfunction "D0_T15") (pintype "bidirectional"))
    )
    (net (code "204") (name "unconnected-(D1E-D1-PadT11)") (class "Default")
      (node (ref "D1") (pin "T11") (pinfunction "D1_T11") (pintype "bidirectional"))
    )
    (net (code "205") (name "unconnected-(D1E-D2-PadU11)") (class "Default")
      (node (ref "D1") (pin "U11") (pinfunction "D2_U11") (pintype "bidirectional"))
    )
    (net (code "206") (name "unconnected-(D1E-D3-PadU12)") (class "Default")
      (node (ref "D1") (pin "U12") (pinfunction "D3_U12") (pintype "bidirectional"))
    )
    (net (code "207") (name "unconnected-(D1E-D6-PadU13)") (class "Default")
      (node (ref "D1") (pin "U13") (pinfunction "D6_U13") (pintype "bidirectional"))
    )
    (net (code "208") (name "unconnected-(D1E-D7-PadV13)") (class "Default")
      (node (ref "D1") (pin "V13") (pinfunction "D7_V13") (pintype "bidirectional"))
    )
    (net (code "209") (name "unconnected-(D1E-D8-PadU14)") (class "Default")
      (node (ref "D1") (pin "U14") (pinfunction "D8_U14") (pintype "bidirectional"))
    )
    (net (code "210") (name "unconnected-(D1E-D9-PadV14)") (class "Default")
      (node (ref "D1") (pin "V14") (pinfunction "D9_V14") (pintype "bidirectional"))
    )
    (net (code "211") (name "unconnected-(D1E-D10-PadU15)") (class "Default")
      (node (ref "D1") (pin "U15") (pinfunction "D10_U15") (pintype "bidirectional"))
    )
    (net (code "212") (name "unconnected-(D1E-D11-PadV15)") (class "Default")
      (node (ref "D1") (pin "V15") (pinfunction "D11_V15") (pintype "bidirectional"))
    )
    (net (code "213") (name "unconnected-(D1E-D12-PadU16)") (class "Default")
      (node (ref "D1") (pin "U16") (pinfunction "D12_U16") (pintype "bidirectional"))
    )
    (net (code "214") (name "unconnected-(D1E-D13-PadV16)") (class "Default")
      (node (ref "D1") (pin "V16") (pinfunction "D13_V16") (pintype "bidirectional"))
    )
    (net (code "215") (name "unconnected-(D1F-G6-PadS9)") (class "Default")
      (node (ref "D1") (pin "S9") (pinfunction "G6_S9") (pintype "bidirectional"))
    )
    (net (code "216") (name "unconnected-(D1F-G7-PadT9)") (class "Default")
      (node (ref "D1") (pin "T9") (pinfunction "G7_T9") (pintype "bidirectional"))
    )
    (net (code "217") (name "unconnected-(D1F-G8-PadU9)") (class "Default")
      (node (ref "D1") (pin "U9") (pinfunction "G8_U9") (pintype "bidirectional"))
    )
    (net (code "218") (name "unconnected-(D1F-G9-PadV9)") (class "Default")
      (node (ref "D1") (pin "V9") (pinfunction "G9_V9") (pintype "bidirectional"))
    )
    (net (code "219") (name "unconnected-(D1F-G10-PadR10)") (class "Default")
      (node (ref "D1") (pin "R10") (pinfunction "G10_R10") (pintype "bidirectional"))
    )
    (net (code "220") (name "unconnected-(D1F-G11-PadS10)") (class "Default")
      (node (ref "D1") (pin "S10") (pinfunction "G11_S10") (pintype "bidirectional"))
    )
    (net (code "221") (name "unconnected-(D1F-G12-PadT10)") (class "Default")
      (node (ref "D1") (pin "T10") (pinfunction "G12_T10") (pintype "bidirectional"))
    )
    (net (code "222") (name "unconnected-(D1F-G13-PadU10)") (class "Default")
      (node (ref "D1") (pin "U10") (pinfunction "G13_U10") (pintype "bidirectional"))
    )
    (net (code "223") (name "unconnected-(D1F-G14-PadV10)") (class "Default")
      (node (ref "D1") (pin "V10") (pinfunction "G14_V10") (pintype "bidirectional"))
    )
    (net (code "224") (name "unconnected-(D1F-G15-PadV11)") (class "Default")
      (node (ref "D1") (pin "V11") (pinfunction "G15_V11") (pintype "bidirectional"))
    )
    (net (code "225") (name "unconnected-(D1F-H0-PadB1)") (class "Default")
      (node (ref "D1") (pin "B1") (pinfunction "H0_B1") (pintype "bidirectional"))
    )
    (net (code "226") (name "unconnected-(D1F-H1-PadC1)") (class "Default")
      (node (ref "D1") (pin "C1") (pinfunction "H1_C1") (pintype "bidirectional"))
    )
    (net (code "227") (name "unconnected-(D1F-H2-PadC2)") (class "Default")
      (node (ref "D1") (pin "C2") (pinfunction "H2_C2") (pintype "bidirectional"))
    )
    (net (code "228") (name "unconnected-(D1F-H3-PadD1)") (class "Default")
      (node (ref "D1") (pin "D1") (pinfunction "H3_D1") (pintype "bidirectional"))
    )
    (net (code "229") (name "unconnected-(D1F-H4-PadD2)") (class "Default")
      (node (ref "D1") (pin "D2") (pinfunction "H4_D2") (pintype "bidirectional"))
    )
    (net (code "230") (name "unconnected-(D1F-H5-PadD3)") (class "Default")
      (node (ref "D1") (pin "D3") (pinfunction "H5_D3") (pintype "bidirectional"))
    )
    (net (code "231") (name "unconnected-(D1F-H6-PadE1)") (class "Default")
      (node (ref "D1") (pin "E1") (pinfunction "H6_E1") (pintype "bidirectional"))
    )
    (net (code "232") (name "unconnected-(D1F-H7-PadE2)") (class "Default")
      (node (ref "D1") (pin "E2") (pinfunction "H7_E2") (pintype "bidirectional"))
    )
    (net (code "233") (name "unconnected-(D1F-H8-PadF1)") (class "Default")
      (node (ref "D1") (pin "F1") (pinfunction "H8_F1") (pintype "bidirectional"))
    )
    (net (code "234") (name "unconnected-(D1F-H9-PadF2)") (class "Default")
      (node (ref "D1") (pin "F2") (pinfunction "H9_F2") (pintype "bidirectional"))
    )
    (net (code "235") (name "unconnected-(D1F-H10-PadF4)") (class "Default")
      (node (ref "D1") (pin "F4") (pinfunction "H10_F4") (pintype "bidirectional"))
    )
    (net (code "236") (name "unconnected-(D1F-H11-PadG1)") (class "Default")
      (node (ref "D1") (pin "G1") (pinfunction "H11_G1") (pintype "bidirectional"))
    )
    (net (code "237") (name "unconnected-(D1F-H12-PadG2)") (class "Default")
      (node (ref "D1") (pin "G2") (pinfunction "H12_G2") (pintype "bidirectional"))
    )
    (net (code "238") (name "unconnected-(D1F-H13-PadG5)") (class "Default")
      (node (ref "D1") (pin "G5") (pinfunction "H13_G5") (pintype "bidirectional"))
    )
    (net (code "239") (name "unconnected-(D1F-H14-PadH1)") (class "Default")
      (node (ref "D1") (pin "H1") (pinfunction "H14_H1") (pintype "bidirectional"))
    )
    (net (code "240") (name "unconnected-(D1F-H15-PadH2)") (class "Default")
      (node (ref "D1") (pin "H2") (pinfunction "H15_H2") (pintype "bidirectional"))
    )
  )
)
